# MCU_ZIGBEE.net
KiCad netlist of a schematic drawn in Altium Designer
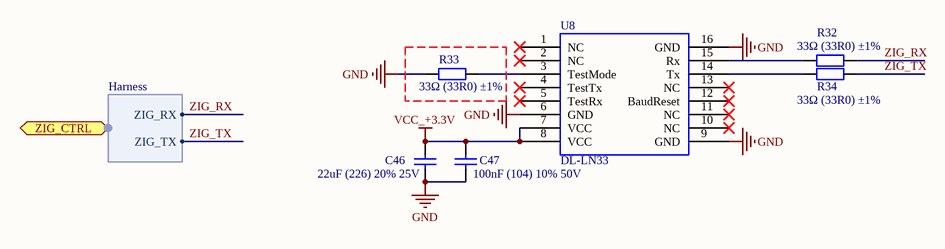
[diagram p0: MCU_ZIGBEE.SchDoc]

(export (version "E")
  (design (tool "Eeschema 10.0.6"))
  (components
    (comp (ref "C46")
      (value "22uF (226) 20% 25V")
      (footprint "LC-0805_C")
      (description "贴片电容")
      (libsource (lib "Miscellaneous Devices LC") (part "0805 22uF (226) 20% 25V"))
    )
    (comp (ref "C47")
      (value "100nF (104) 10% 50V")
      (footprint "LC-0603_C")
      (description "贴片电容")
      (libsource (lib "Miscellaneous Devices LC") (part "0603 100nF (104) 10% 50V"))
    )
    (comp (ref "R32")
      (value "33Ω (33R0) ±1%")
      (footprint "LC-0603_R")
      (description "贴片电阻")
      (libsource (lib "Miscellaneous Devices LC") (part "0603 33Ω (33R0) 1%"))
    )
    (comp (ref "R33")
      (value "33Ω (33R0) ±1%")
      (footprint "LC-0603_R")
      (description "贴片电阻")
      (libsource (lib "Miscellaneous Devices LC") (part "0603 33Ω (33R0) 1%"))
    )
    (comp (ref "R34")
      (value "33Ω (33R0) ±1%")
      (footprint "LC-0603_R")
      (description "贴片电阻")
      (libsource (lib "Miscellaneous Devices LC") (part "0603 33Ω (33R0) 1%"))
    )
    (comp (ref "U8")
      (value "DL-LN33")
      (footprint "RCM-DL-LN33")
      (description "Zigbee 2.4G Multi-hop AdHos WSN Modules")
      (libsource (lib "Altium_schematic_lib") (part "DL-LN3X"))
    )
  )
  (nets
    (net (code "2") (name "/ZIG_RX") (class "Default")
      (node (ref "R32") (pin "2") (pinfunction "2_2") (pintype "passive"))
    )
    (net (code "3") (name "/ZIG_TX") (class "Default")
      (node (ref "R34") (pin "2") (pinfunction "2_2") (pintype "passive"))
    )
    (net (code "5") (name "GND") (class "Default")
      (node (ref "C46") (pin "1") (pinfunction "1_1") (pintype "passive"))
      (node (ref "C47") (pin "1") (pinfunction "1_1") (pintype "passive"))
      (node (ref "R33") (pin "1") (pinfunction "1_1") (pintype "passive"))
      (node (ref "U8") (pin "16") (pinfunction "GND_16") (pintype "passive"))
      (node (ref "U8") (pin "6") (pinfunction "GND_6") (pintype "passive"))
      (node (ref "U8") (pin "9") (pinfunction "GND_9") (pintype "passive"))
    )
    (net (code "6") (name "Net-(U8-Rx)") (class "Default")
      (node (ref "R32") (pin "1") (pinfunction "1_1") (pintype "passive"))
      (node (ref "U8") (pin "15") (pinfunction "Rx_15") (pintype "passive"))
    )
    (net (code "7") (name "Net-(U8-TestMode)") (class "Default")
      (node (ref "R33") (pin "2") (pinfunction "2_2") (pintype "passive"))
      (node (ref "U8") (pin "3") (pinfunction "TestMode_3") (pintype "passive"))
    )
    (net (code "8") (name "Net-(U8-Tx)") (class "Default")
      (node (ref "R34") (pin "1") (pinfunction "1_1") (pintype "passive"))
      (node (ref "U8") (pin "14") (pinfunction "Tx_14") (pintype "passive"))
    )
    (net (code "9") (name "VCC_+3.3V") (class "Default")
      (node (ref "C46") (pin "2") (pinfunction "2_2") (pintype "passive"))
      (node (ref "C47") (pin "2") (pinfunction "2_2") (pintype "passive"))
      (node (ref "U8") (pin "7") (pinfunction "VCC_7") (pintype "passive"))
      (node (ref "U8") (pin "8") (pinfunction "VCC_8") (pintype "passive"))
    )
    (net (code "10") (name "unconnected-(U8-BaudReset-Pad12)") (class "Default")
      (node (ref "U8") (pin "12") (pinfunction "BaudReset_12") (pintype "passive+no_connect"))
    )
    (net (code "11") (name "unconnected-(U8-NC-Pad1)") (class "Default")
      (node (ref "U8") (pin "1") (pinfunction "NC_1") (pintype "passive+no_connect"))
    )
    (net (code "12") (name "unconnected-(U8-NC-Pad2)") (class "Default")
      (node (ref "U8") (pin "2") (pinfunction "NC_2") (pintype "passive+no_connect"))
    )
    (net (code "13") (name "unconnected-(U8-NC-Pad10)") (class "Default")
      (node (ref "U8") (pin "10") (pinfunction "NC_10") (pintype "passive+no_connect"))
    )
    (net (code "14") (name "unconnected-(U8-NC-Pad11)") (class "Default")
      (node (ref "U8") (pin "11") (pinfunction "NC_11") (pintype "passive+no_connect"))
    )
    (net (code "15") (name "unconnected-(U8-NC-Pad13)") (class "Default")
      (node (ref "U8") (pin "13") (pinfunction "NC_13") (pintype "passive+no_connect"))
    )
    (net (code "16") (name "unconnected-(U8-TestRx-Pad5)") (class "Default")
      (node (ref "U8") (pin "5") (pinfunction "TestRx_5") (pintype "passive+no_connect"))
    )
    (net (code "17") (name "unconnected-(U8-TestTx-Pad4)") (class "Default")
      (node (ref "U8") (pin "4") (pinfunction "TestTx_4") (pintype "passive+no_connect"))
    )
  )
)
